# PCA9632_4-Ch_LED_Driver.net
KiCad netlist of a schematic drawn in Altium Designer
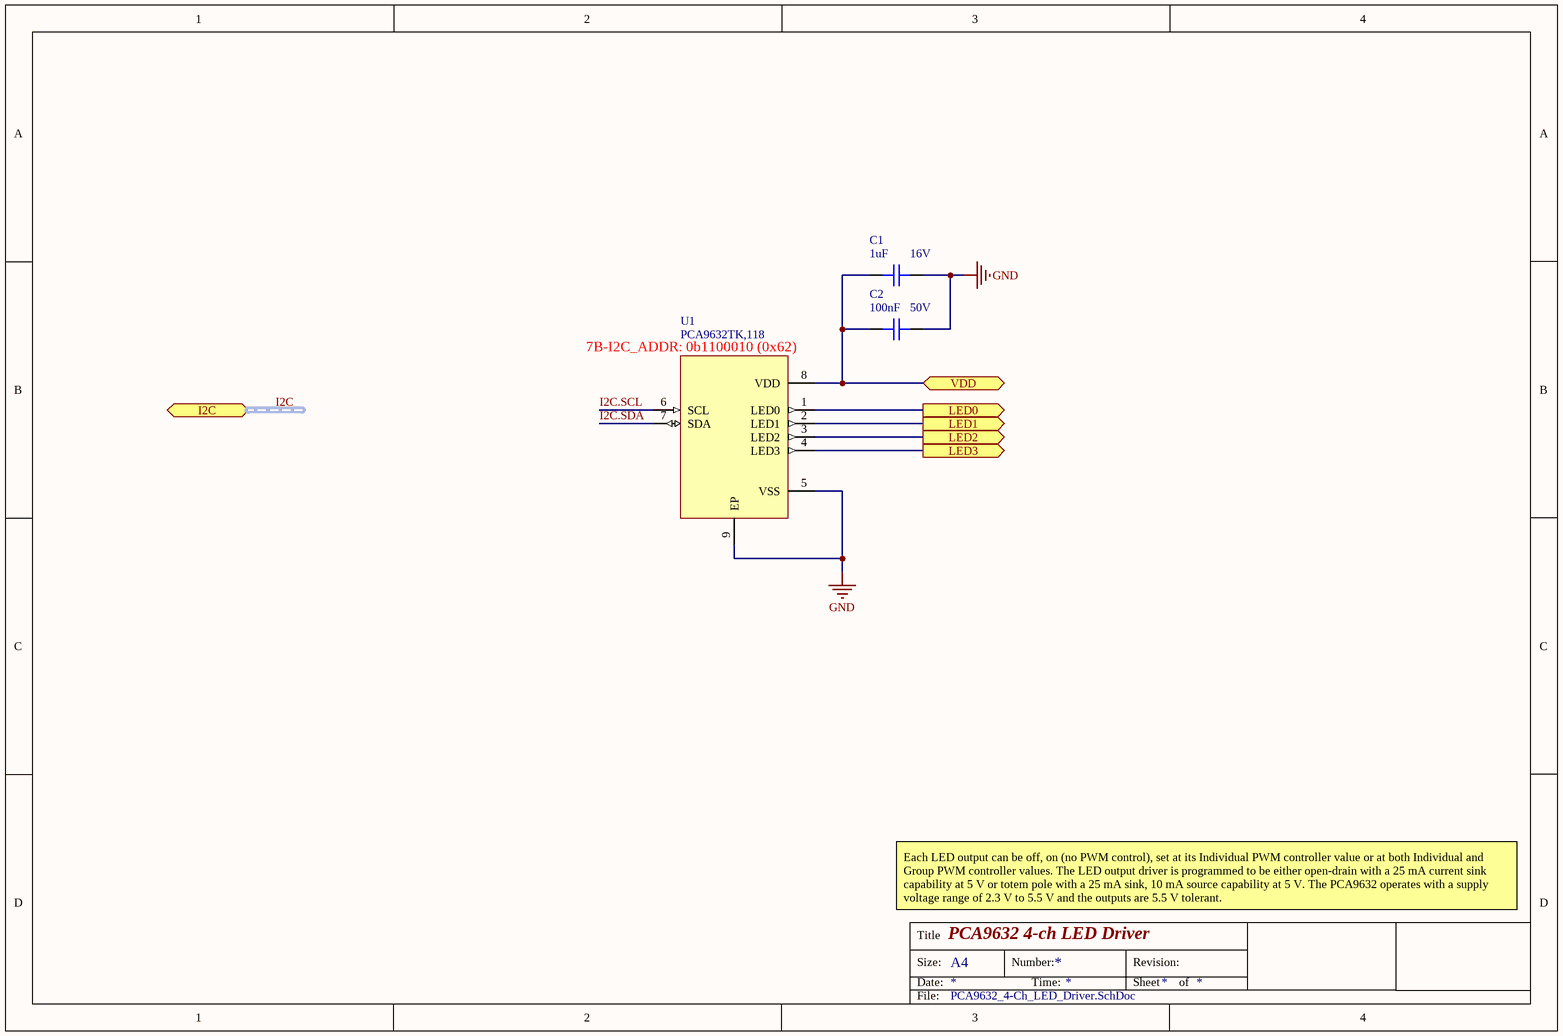
[diagram p0: PCA9632_4-Ch_LED_Driver.SchDoc]

(export (version "E")
  (design (tool "Eeschema 10.0.6"))
  (components
    (comp (ref "C1")
      (value "CAP CER 1UF 16V X5R 0402")
      (footprint "C0402")
      (description "1µF ±10% 16V Ceramic Capacitor X5R 0402 (1005 Metric)")
      (fields
        (field (name "MANUFACTURER") "Yageo")
        (field (name "MANUFACTURER PART NUMBER") "CC0402KRX5R7BB105")
        (field (name "CAPACITANCE") "1uF")
        (field (name "VOLTAGE RATING") "16V")
      )
      (libsource (lib "capacitors_smd") (part "CAP CER 1UF 16V X5R 0402"))
    )
    (comp (ref "C2")
      (value "CAP CER 0.1UF 50V X7R 0402")
      (footprint "C0402")
      (description "0.1µF ±10% 50V Ceramic Capacitor X7R 0402 (1005 Metric)")
      (fields
        (field (name "MANUFACTURER") "TDK")
        (field (name "MANUFACTURER PART NUMBER") "CGA2B3X7R1H104K050BB")
        (field (name "CAPACITANCE") "100nF")
        (field (name "VOLTAGE") "50V")
      )
      (libsource (lib "capacitors_smd") (part "CAP CER 0.1UF 50V X7R 0402"))
    )
    (comp (ref "U1")
      (value "PCA9632TK,118")
      (footprint "SOT908-1")
      (description "LED Driver IC 4 Output Power Switch  PWM Dimming 25mA 8-HVSON (3x3)")
      (fields
        (field (name "MANUFACTURER") "NXP Semiconductors")
        (field (name "7B-I2C_ADDR") "0b1100010 (0x62)")
      )
      (libsource (lib "BLDC_Motor_Driver") (part "IC PCA9632TK,118 LED DRVR LIN DIM 25MA 8HVSON"))
    )
  )
  (nets
    (net (code "2") (name "/I2C.SCL") (class "Default")
      (node (ref "U1") (pin "6") (pinfunction "SCL_6") (pintype "input"))
    )
    (net (code "3") (name "/I2C.SDA") (class "Default")
      (node (ref "U1") (pin "7") (pinfunction "SDA_7") (pintype "bidirectional"))
    )
    (net (code "4") (name "/LED0") (class "Default")
      (node (ref "U1") (pin "1") (pinfunction "LED0_1") (pintype "output"))
    )
    (net (code "5") (name "/LED1") (class "Default")
      (node (ref "U1") (pin "2") (pinfunction "LED1_2") (pintype "output"))
    )
    (net (code "6") (name "/LED2") (class "Default")
      (node (ref "U1") (pin "3") (pinfunction "LED2_3") (pintype "output"))
    )
    (net (code "7") (name "/LED3") (class "Default")
      (node (ref "U1") (pin "4") (pinfunction "LED3_4") (pintype "output"))
    )
    (net (code "8") (name "/VDD") (class "Default")
      (node (ref "C1") (pin "2") (pinfunction "2_2") (pintype "passive"))
      (node (ref "C2") (pin "2") (pinfunction "2_2") (pintype "passive"))
      (node (ref "U1") (pin "8") (pinfunction "VDD_8") (pintype "power_in"))
    )
    (net (code "10") (name "GND") (class "Default")
      (node (ref "C1") (pin "1") (pinfunction "1_1") (pintype "passive"))
      (node (ref "C2") (pin "1") (pinfunction "1_1") (pintype "passive"))
      (node (ref "U1") (pin "5") (pinfunction "VSS_5") (pintype "power_in"))
      (node (ref "U1") (pin "9") (pinfunction "EP_9") (pintype "power_in"))
    )
  )
)
